# Review_PCD_1_7.net
KiCad netlist of a schematic drawn in EAGLE
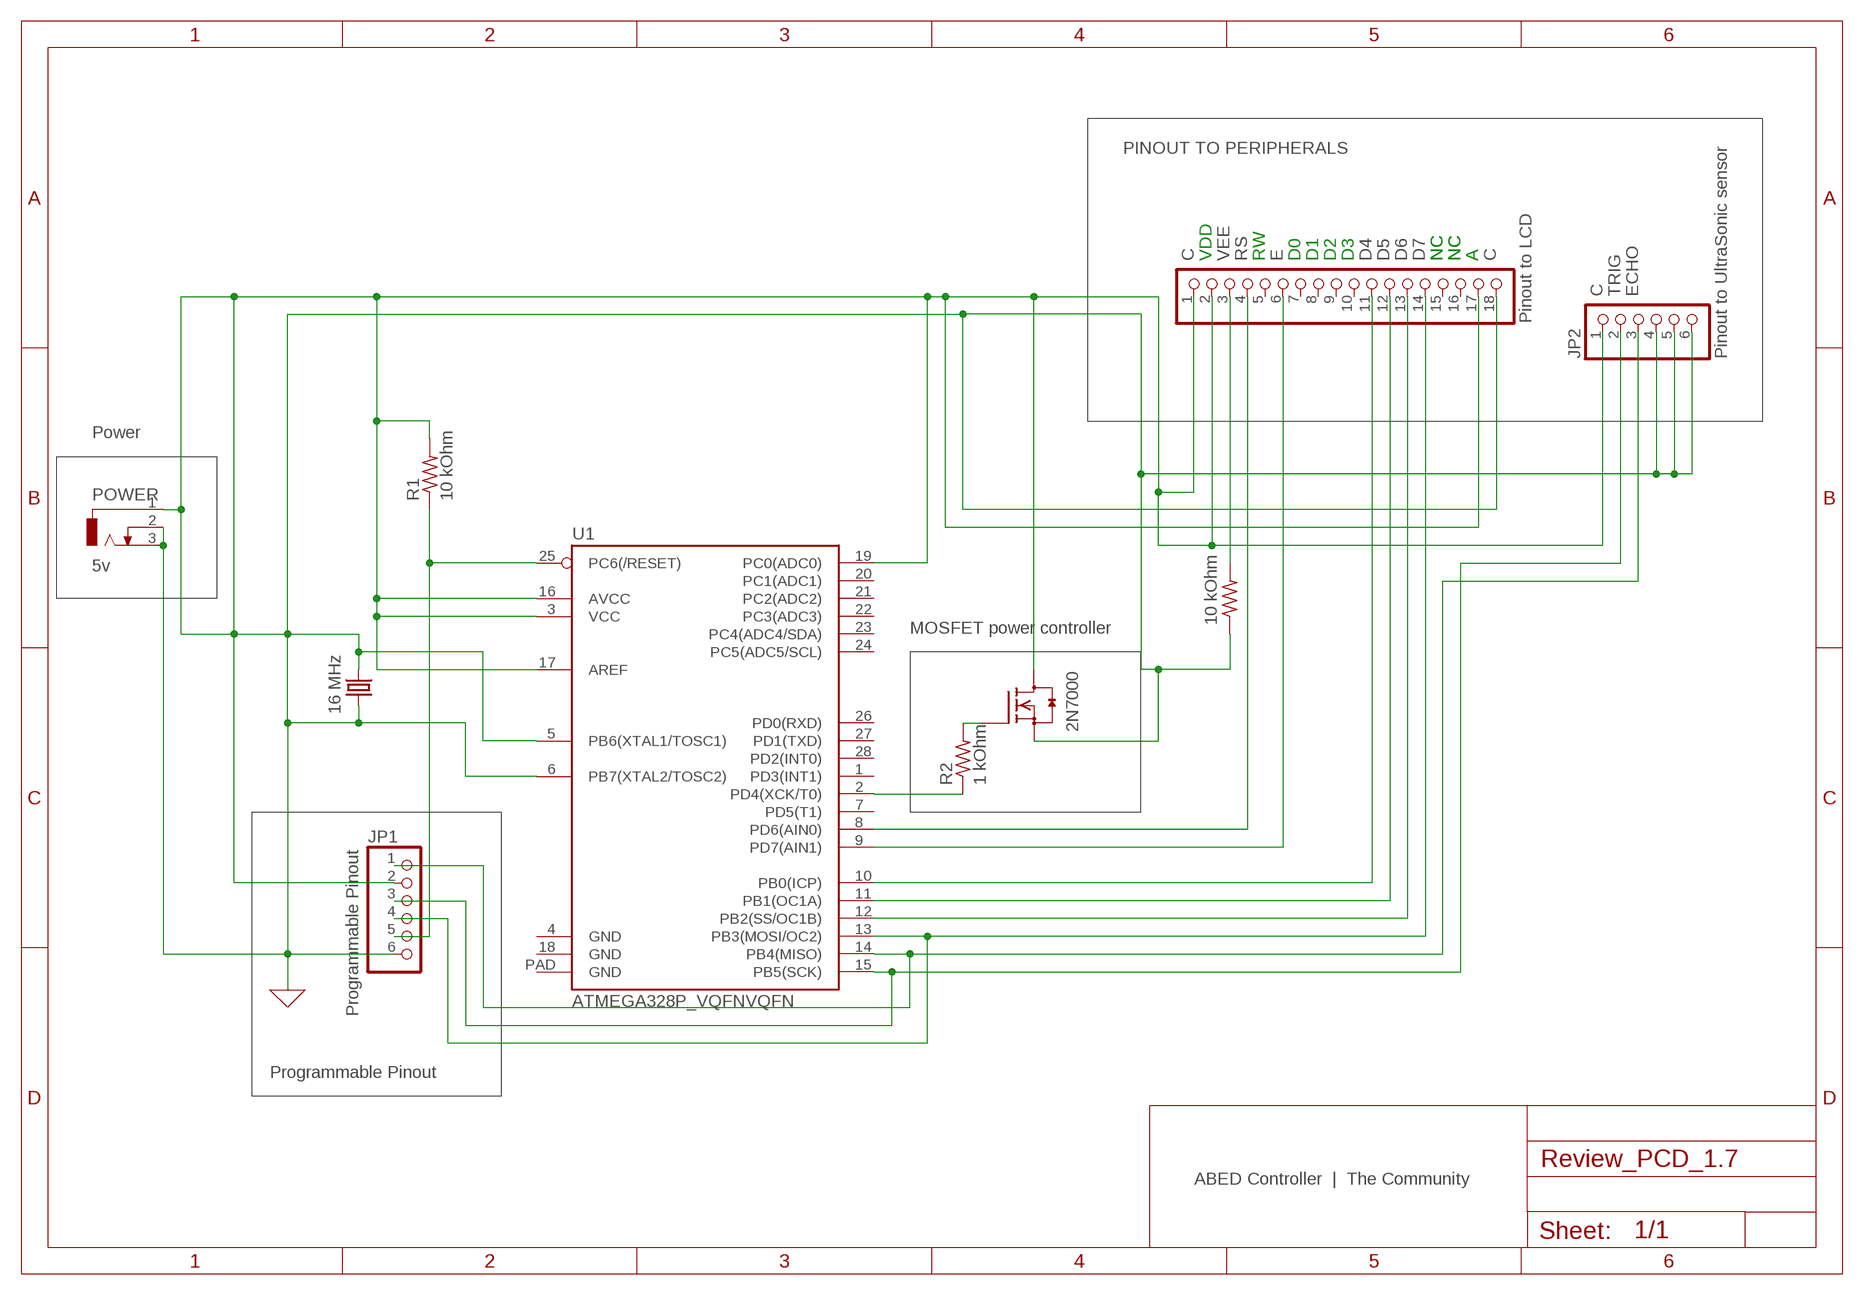
[diagram p0: schematic, sheet 1]

(export (version "E")
  (design (tool "Eeschema 10.0.6"))
  (components
    (comp (ref "JP1")
      (value "Programmable Pinout")
      (footprint "eagle-import:1X06-3.5MM")
      (libsource (lib "eagle-import") (part "PINHD-1X6-3.5MM"))
    )
    (comp (ref "JP2")
      (value "Pinout to UltraSonic sensor")
      (footprint "eagle-import:1X06-BIG")
      (libsource (lib "eagle-import") (part "PINHD-1X6B"))
    )
    (comp (ref "JP3")
      (value "Pinout to LCD")
      (footprint "eagle-import:1X18")
      (libsource (lib "eagle-import") (part "PINHD-1X18"))
    )
    (comp (ref "POWER")
      (value "5v")
      (footprint "eagle-import:DCJ0202")
      (libsource (lib "eagle-import") (part "DCJ0202"))
    )
    (comp (ref "Q1")
      (value "16 MHz")
      (footprint "eagle-import:1.6X1.2")
      (fields (field (name "Q1") "16 MHz"))
      (libsource (lib "eagle-import") (part "KX-4"))
    )
    (comp (ref "Q2")
      (value "2N7000")
      (footprint "eagle-import:TO92")
      (libsource (lib "eagle-import") (part "2N7000KL/BS170KL"))
    )
    (comp (ref "R1")
      (value "10 kOhm")
      (footprint "eagle-import:R2012W")
      (libsource (lib "eagle-import") (part "R-US_R2012W"))
    )
    (comp (ref "R2")
      (value "1 kOhm")
      (footprint "eagle-import:R2012W")
      (fields (field (name "R1") "1 kOhm"))
      (libsource (lib "eagle-import") (part "R-US_R2012W"))
    )
    (comp (ref "R3")
      (value "10 kOhm")
      (footprint "eagle-import:R2012W")
      (fields (field (name "R1") "10 kOhm"))
      (libsource (lib "eagle-import") (part "R-US_R2012W"))
    )
    (comp (ref "U1")
      (value "ATMEGA328P_VQFNVQFN")
      (footprint "eagle-import:VQFN-28")
      (libsource (lib "eagle-import") (part "ATMEGA328P_VQFNVQFN"))
    )
  )
  (nets
    (net (code "1") (name "/D4") (class "Default")
      (node (ref "JP3") (pin "11") (pinfunction "11_11") (pintype "passive"))
      (node (ref "U1") (pin "10") (pinfunction "PB0(ICP)_10") (pintype "bidirectional"))
    )
    (net (code "2") (name "/D5") (class "Default")
      (node (ref "JP3") (pin "12") (pinfunction "12_12") (pintype "passive"))
      (node (ref "U1") (pin "11") (pinfunction "PB1(OC1A)_11") (pintype "bidirectional"))
    )
    (net (code "3") (name "/D6") (class "Default")
      (node (ref "JP3") (pin "13") (pinfunction "13_13") (pintype "passive"))
      (node (ref "U1") (pin "12") (pinfunction "PB2(SS/OC1B)_12") (pintype "bidirectional"))
    )
    (net (code "4") (name "/D7") (class "Default")
      (node (ref "JP1") (pin "4") (pinfunction "4_4") (pintype "passive"))
      (node (ref "JP3") (pin "14") (pinfunction "14_14") (pintype "passive"))
      (node (ref "U1") (pin "13") (pinfunction "PB3(MOSI/OC2)_13") (pintype "bidirectional"))
    )
    (net (code "5") (name "/E") (class "Default")
      (node (ref "JP3") (pin "6") (pinfunction "6_6") (pintype "passive"))
      (node (ref "U1") (pin "9") (pinfunction "PD7(AIN1)_9") (pintype "bidirectional"))
    )
    (net (code "6") (name "/ECHO") (class "Default")
      (node (ref "JP1") (pin "1") (pinfunction "1_1") (pintype "passive"))
      (node (ref "JP2") (pin "3") (pinfunction "3_3") (pintype "passive"))
      (node (ref "U1") (pin "14") (pinfunction "PB4(MISO)_14") (pintype "bidirectional"))
    )
    (net (code "7") (name "/RS") (class "Default")
      (node (ref "JP3") (pin "4") (pinfunction "4_4") (pintype "passive"))
      (node (ref "U1") (pin "8") (pinfunction "PD6(AIN0)_8") (pintype "bidirectional"))
    )
    (net (code "8") (name "/TRIG") (class "Default")
      (node (ref "JP1") (pin "3") (pinfunction "3_3") (pintype "passive"))
      (node (ref "JP2") (pin "2") (pinfunction "2_2") (pintype "passive"))
      (node (ref "U1") (pin "15") (pinfunction "PB5(SCK)_15") (pintype "bidirectional"))
    )
    (net (code "9") (name "/VEE") (class "Default")
      (node (ref "JP3") (pin "3") (pinfunction "3_3") (pintype "passive"))
      (node (ref "R3") (pin "2") (pinfunction "2_2") (pintype "passive"))
    )
    (net (code "10") (name "GND") (class "Default")
      (node (ref "JP1") (pin "2") (pinfunction "2_2") (pintype "passive"))
      (node (ref "JP1") (pin "6") (pinfunction "6_6") (pintype "passive"))
      (node (ref "JP2") (pin "1") (pinfunction "1_1") (pintype "passive"))
      (node (ref "JP2") (pin "4") (pinfunction "4_4") (pintype "passive"))
      (node (ref "JP2") (pin "5") (pinfunction "5_5") (pintype "passive"))
      (node (ref "JP2") (pin "6") (pinfunction "6_6") (pintype "passive"))
      (node (ref "JP3") (pin "1") (pinfunction "1_1") (pintype "passive"))
      (node (ref "JP3") (pin "17") (pinfunction "17_17") (pintype "passive"))
      (node (ref "JP3") (pin "18") (pinfunction "18_18") (pintype "passive"))
      (node (ref "JP3") (pin "2") (pinfunction "2_2") (pintype "passive"))
      (node (ref "POWER") (pin "1") (pinfunction "1_1") (pintype "passive"))
      (node (ref "POWER") (pin "2") (pinfunction "2_2") (pintype "passive"))
      (node (ref "POWER") (pin "3") (pinfunction "3_3") (pintype "passive"))
      (node (ref "Q1") (pin "1") (pinfunction "1_1") (pintype "passive"))
      (node (ref "Q1") (pin "3") (pinfunction "2_3") (pintype "passive"))
      (node (ref "Q2") (pin "1") (pinfunction "S_1") (pintype "passive"))
      (node (ref "Q2") (pin "3") (pinfunction "D_3") (pintype "passive"))
      (node (ref "R1") (pin "2") (pinfunction "2_2") (pintype "passive"))
      (node (ref "R3") (pin "1") (pinfunction "1_1") (pintype "passive"))
      (node (ref "U1") (pin "16") (pinfunction "AVCC_16") (pintype "bidirectional"))
      (node (ref "U1") (pin "17") (pinfunction "AREF_17") (pintype "bidirectional"))
      (node (ref "U1") (pin "19") (pinfunction "PC0(ADC0)_19") (pintype "bidirectional"))
      (node (ref "U1") (pin "3") (pinfunction "VCC_3") (pintype "bidirectional"))
      (node (ref "U1") (pin "5") (pinfunction "PB6(XTAL1/TOSC1)_5") (pintype "bidirectional"))
      (node (ref "U1") (pin "6") (pinfunction "PB7(XTAL2/TOSC2)_6") (pintype "bidirectional"))
    )
    (net (code "11") (name "Net-(Q2-G)") (class "Default")
      (node (ref "Q2") (pin "2") (pinfunction "G_2") (pintype "passive"))
      (node (ref "R2") (pin "2") (pinfunction "2_2") (pintype "passive"))
    )
    (net (code "12") (name "Net-(U1-PC6({slash}RESET))") (class "Default")
      (node (ref "JP1") (pin "5") (pinfunction "5_5") (pintype "passive"))
      (node (ref "R1") (pin "1") (pinfunction "1_1") (pintype "passive"))
      (node (ref "U1") (pin "25") (pinfunction "PC6(/RESET)_25") (pintype "bidirectional"))
    )
    (net (code "13") (name "Net-(U1-PD4(XCK{slash}T0))") (class "Default")
      (node (ref "R2") (pin "1") (pinfunction "1_1") (pintype "passive"))
      (node (ref "U1") (pin "2") (pinfunction "PD4(XCK/T0)_2") (pintype "bidirectional"))
    )
    (net (code "14") (name "unconnected-(JP3-Pad5)") (class "Default")
      (node (ref "JP3") (pin "5") (pinfunction "5_5") (pintype "passive"))
    )
    (net (code "15") (name "unconnected-(JP3-Pad7)") (class "Default")
      (node (ref "JP3") (pin "7") (pinfunction "7_7") (pintype "passive"))
    )
    (net (code "16") (name "unconnected-(JP3-Pad8)") (class "Default")
      (node (ref "JP3") (pin "8") (pinfunction "8_8") (pintype "passive"))
    )
    (net (code "17") (name "unconnected-(JP3-Pad9)") (class "Default")
      (node (ref "JP3") (pin "9") (pinfunction "9_9") (pintype "passive"))
    )
    (net (code "18") (name "unconnected-(JP3-Pad10)") (class "Default")
      (node (ref "JP3") (pin "10") (pinfunction "10_10") (pintype "passive"))
    )
    (net (code "19") (name "unconnected-(JP3-Pad15)") (class "Default")
      (node (ref "JP3") (pin "15") (pinfunction "15_15") (pintype "passive"))
    )
    (net (code "20") (name "unconnected-(JP3-Pad16)") (class "Default")
      (node (ref "JP3") (pin "16") (pinfunction "16_16") (pintype "passive"))
    )
    (net (code "21") (name "unconnected-(U1-GND-Pad4)") (class "Default")
      (node (ref "U1") (pin "4") (pinfunction "GND_4") (pintype "bidirectional"))
    )
    (net (code "22") (name "unconnected-(U1-GND-Pad18)") (class "Default")
      (node (ref "U1") (pin "18") (pinfunction "GND_18") (pintype "bidirectional"))
    )
    (net (code "23") (name "unconnected-(U1-GND-PadPAD)") (class "Default")
      (node (ref "U1") (pin "PAD") (pinfunction "GND_PAD") (pintype "bidirectional"))
    )
    (net (code "24") (name "unconnected-(U1-PC1(ADC1)-Pad20)") (class "Default")
      (node (ref "U1") (pin "20") (pinfunction "PC1(ADC1)_20") (pintype "bidirectional"))
    )
    (net (code "25") (name "unconnected-(U1-PC2(ADC2)-Pad21)") (class "Default")
      (node (ref "U1") (pin "21") (pinfunction "PC2(ADC2)_21") (pintype "bidirectional"))
    )
    (net (code "26") (name "unconnected-(U1-PC3(ADC3)-Pad22)") (class "Default")
      (node (ref "U1") (pin "22") (pinfunction "PC3(ADC3)_22") (pintype "bidirectional"))
    )
    (net (code "27") (name "unconnected-(U1-PC4(ADC4{slash}SDA)-Pad23)") (class "Default")
      (node (ref "U1") (pin "23") (pinfunction "PC4(ADC4/SDA)_23") (pintype "bidirectional"))
    )
    (net (code "28") (name "unconnected-(U1-PC5(ADC5{slash}SCL)-Pad24)") (class "Default")
      (node (ref "U1") (pin "24") (pinfunction "PC5(ADC5/SCL)_24") (pintype "bidirectional"))
    )
    (net (code "29") (name "unconnected-(U1-PD0(RXD)-Pad26)") (class "Default")
      (node (ref "U1") (pin "26") (pinfunction "PD0(RXD)_26") (pintype "bidirectional"))
    )
    (net (code "30") (name "unconnected-(U1-PD1(TXD)-Pad27)") (class "Default")
      (node (ref "U1") (pin "27") (pinfunction "PD1(TXD)_27") (pintype "bidirectional"))
    )
    (net (code "31") (name "unconnected-(U1-PD2(INT0)-Pad28)") (class "Default")
      (node (ref "U1") (pin "28") (pinfunction "PD2(INT0)_28") (pintype "bidirectional"))
    )
    (net (code "32") (name "unconnected-(U1-PD3(INT1)-Pad1)") (class "Default")
      (node (ref "U1") (pin "1") (pinfunction "PD3(INT1)_1") (pintype "bidirectional"))
    )
    (net (code "33") (name "unconnected-(U1-PD5(T1)-Pad7)") (class "Default")
      (node (ref "U1") (pin "7") (pinfunction "PD5(T1)_7") (pintype "bidirectional"))
    )
  )
)
